# relays0_jaanuse-raal_s_conflicted_copy_2.net
KiCad netlist of a schematic drawn in Altium Designer
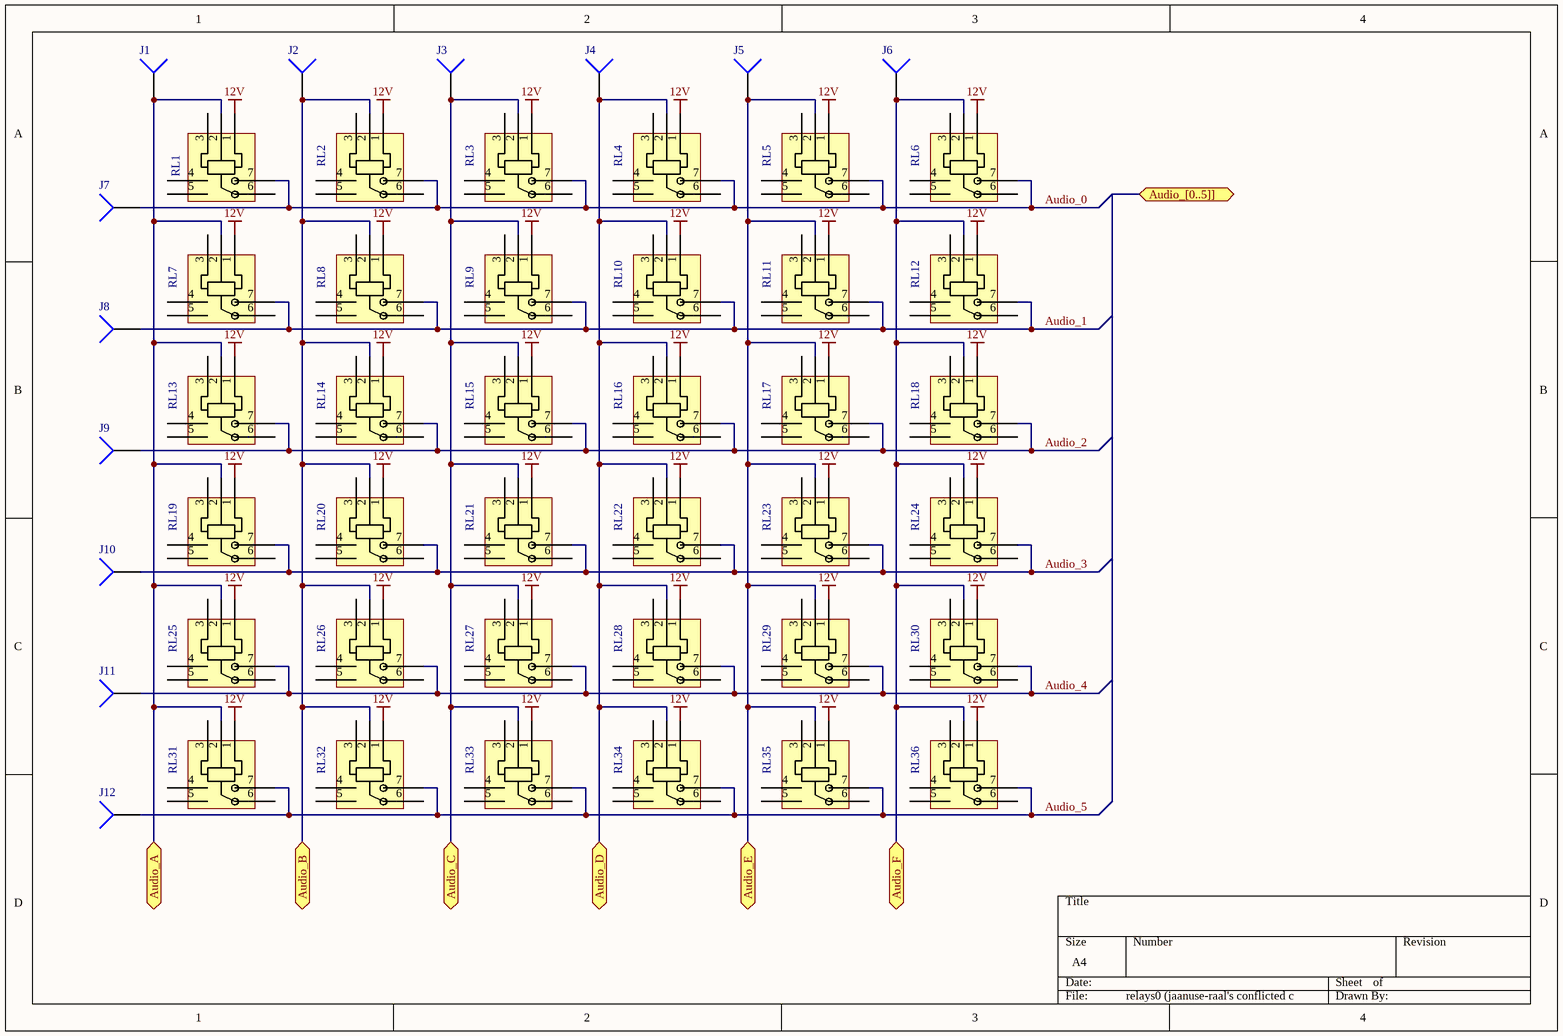
[diagram p0: relays0 (jaanuse-raal's conflicted copy 2014-11-12).SchDoc]

(export (version "E")
  (design (tool "Eeschema 10.0.6"))
  (components
    (comp (ref "J1")
      (value "Audio")
      (footprint "PIN1")
      (description "Socket")
      (fields (field (name "PUBLISHER") "Altium Limited"))
      (libsource (lib "Miscellaneous Connectors") (part "Socket"))
    )
    (comp (ref "J2")
      (value "Audio")
      (footprint "PIN1")
      (description "Socket")
      (fields (field (name "PUBLISHER") "Altium Limited"))
      (libsource (lib "Miscellaneous Connectors") (part "Socket"))
    )
    (comp (ref "J3")
      (value "Audio")
      (footprint "PIN1")
      (description "Socket")
      (fields (field (name "PUBLISHER") "Altium Limited"))
      (libsource (lib "Miscellaneous Connectors") (part "Socket"))
    )
    (comp (ref "J4")
      (value "Audio")
      (footprint "PIN1")
      (description "Socket")
      (fields (field (name "PUBLISHER") "Altium Limited"))
      (libsource (lib "Miscellaneous Connectors") (part "Socket"))
    )
    (comp (ref "J5")
      (value "Audio")
      (footprint "PIN1")
      (description "Socket")
      (fields (field (name "PUBLISHER") "Altium Limited"))
      (libsource (lib "Miscellaneous Connectors") (part "Socket"))
    )
    (comp (ref "J6")
      (value "Audio")
      (footprint "PIN1")
      (description "Socket")
      (fields (field (name "PUBLISHER") "Altium Limited"))
      (libsource (lib "Miscellaneous Connectors") (part "Socket"))
    )
    (comp (ref "J7")
      (value "Audio")
      (footprint "PIN1")
      (description "Socket")
      (fields (field (name "PUBLISHER") "Altium Limited"))
      (libsource (lib "Miscellaneous Connectors") (part "Socket"))
    )
    (comp (ref "J8")
      (value "Audio")
      (footprint "PIN1")
      (description "Socket")
      (fields (field (name "PUBLISHER") "Altium Limited"))
      (libsource (lib "Miscellaneous Connectors") (part "Socket"))
    )
    (comp (ref "J9")
      (value "Audio")
      (footprint "PIN1")
      (description "Socket")
      (fields (field (name "PUBLISHER") "Altium Limited"))
      (libsource (lib "Miscellaneous Connectors") (part "Socket"))
    )
    (comp (ref "J10")
      (value "Audio")
      (footprint "PIN1")
      (description "Socket")
      (fields (field (name "PUBLISHER") "Altium Limited"))
      (libsource (lib "Miscellaneous Connectors") (part "Socket"))
    )
    (comp (ref "J11")
      (value "Audio")
      (footprint "PIN1")
      (description "Socket")
      (fields (field (name "PUBLISHER") "Altium Limited"))
      (libsource (lib "Miscellaneous Connectors") (part "Socket"))
    )
    (comp (ref "J12")
      (value "Audio")
      (footprint "PIN1")
      (description "Socket")
      (fields (field (name "PUBLISHER") "Altium Limited"))
      (libsource (lib "Miscellaneous Connectors") (part "Socket"))
    )
    (comp (ref "RL1")
      (value "Relay")
      (footprint "Relay_FRA3")
      (description "Miniature power relay")
      (fields (field (name "PART NUMBER") "FRA3C-DC12"))
      (libsource (lib "tech-thing") (part "Relay_FRA3"))
    )
    (comp (ref "RL2")
      (value "Relay")
      (footprint "Relay_FRA3")
      (description "Miniature power relay")
      (fields (field (name "PART NUMBER") "FRA3C-DC12"))
      (libsource (lib "tech-thing") (part "Relay_FRA3"))
    )
    (comp (ref "RL3")
      (value "Relay")
      (footprint "Relay_FRA3")
      (description "Miniature power relay")
      (fields (field (name "PART NUMBER") "FRA3C-DC12"))
      (libsource (lib "tech-thing") (part "Relay_FRA3"))
    )
    (comp (ref "RL4")
      (value "Relay")
      (footprint "Relay_FRA3")
      (description "Miniature power relay")
      (fields (field (name "PART NUMBER") "FRA3C-DC12"))
      (libsource (lib "tech-thing") (part "Relay_FRA3"))
    )
    (comp (ref "RL5")
      (value "Relay")
      (footprint "Relay_FRA3")
      (description "Miniature power relay")
      (fields (field (name "PART NUMBER") "FRA3C-DC12"))
      (libsource (lib "tech-thing") (part "Relay_FRA3"))
    )
    (comp (ref "RL6")
      (value "Relay")
      (footprint "Relay_FRA3")
      (description "Miniature power relay")
      (fields (field (name "PART NUMBER") "FRA3C-DC12"))
      (libsource (lib "tech-thing") (part "Relay_FRA3"))
    )
    (comp (ref "RL7")
      (value "Relay")
      (footprint "Relay_FRA3")
      (description "Miniature power relay")
      (fields (field (name "PART NUMBER") "FRA3C-DC12"))
      (libsource (lib "tech-thing") (part "Relay_FRA3"))
    )
    (comp (ref "RL8")
      (value "Relay")
      (footprint "Relay_FRA3")
      (description "Miniature power relay")
      (fields (field (name "PART NUMBER") "FRA3C-DC12"))
      (libsource (lib "tech-thing") (part "Relay_FRA3"))
    )
    (comp (ref "RL9")
      (value "Relay")
      (footprint "Relay_FRA3")
      (description "Miniature power relay")
      (fields (field (name "PART NUMBER") "FRA3C-DC12"))
      (libsource (lib "tech-thing") (part "Relay_FRA3"))
    )
    (comp (ref "RL10")
      (value "Relay")
      (footprint "Relay_FRA3")
      (description "Miniature power relay")
      (fields (field (name "PART NUMBER") "FRA3C-DC12"))
      (libsource (lib "tech-thing") (part "Relay_FRA3"))
    )
    (comp (ref "RL11")
      (value "Relay")
      (footprint "Relay_FRA3")
      (description "Miniature power relay")
      (fields (field (name "PART NUMBER") "FRA3C-DC12"))
      (libsource (lib "tech-thing") (part "Relay_FRA3"))
    )
    (comp (ref "RL12")
      (value "Relay")
      (footprint "Relay_FRA3")
      (description "Miniature power relay")
      (fields (field (name "PART NUMBER") "FRA3C-DC12"))
      (libsource (lib "tech-thing") (part "Relay_FRA3"))
    )
    (comp (ref "RL13")
      (value "Relay")
      (footprint "Relay_FRA3")
      (description "Miniature power relay")
      (fields (field (name "PART NUMBER") "FRA3C-DC12"))
      (libsource (lib "tech-thing") (part "Relay_FRA3"))
    )
    (comp (ref "RL14")
      (value "Relay")
      (footprint "Relay_FRA3")
      (description "Miniature power relay")
      (fields (field (name "PART NUMBER") "FRA3C-DC12"))
      (libsource (lib "tech-thing") (part "Relay_FRA3"))
    )
    (comp (ref "RL15")
      (value "Relay")
      (footprint "Relay_FRA3")
      (description "Miniature power relay")
      (fields (field (name "PART NUMBER") "FRA3C-DC12"))
      (libsource (lib "tech-thing") (part "Relay_FRA3"))
    )
    (comp (ref "RL16")
      (value "Relay")
      (footprint "Relay_FRA3")
      (description "Miniature power relay")
      (fields (field (name "PART NUMBER") "FRA3C-DC12"))
      (libsource (lib "tech-thing") (part "Relay_FRA3"))
    )
    (comp (ref "RL17")
      (value "Relay")
      (footprint "Relay_FRA3")
      (description "Miniature power relay")
      (fields (field (name "PART NUMBER") "FRA3C-DC12"))
      (libsource (lib "tech-thing") (part "Relay_FRA3"))
    )
    (comp (ref "RL18")
      (value "Relay")
      (footprint "Relay_FRA3")
      (description "Miniature power relay")
      (fields (field (name "PART NUMBER") "FRA3C-DC12"))
      (libsource (lib "tech-thing") (part "Relay_FRA3"))
    )
    (comp (ref "RL19")
      (value "Relay")
      (footprint "Relay_FRA3")
      (description "Miniature power relay")
      (fields (field (name "PART NUMBER") "FRA3C-DC12"))
      (libsource (lib "tech-thing") (part "Relay_FRA3"))
    )
    (comp (ref "RL20")
      (value "Relay")
      (footprint "Relay_FRA3")
      (description "Miniature power relay")
      (fields (field (name "PART NUMBER") "FRA3C-DC12"))
      (libsource (lib "tech-thing") (part "Relay_FRA3"))
    )
    (comp (ref "RL21")
      (value "Relay")
      (footprint "Relay_FRA3")
      (description "Miniature power relay")
      (fields (field (name "PART NUMBER") "FRA3C-DC12"))
      (libsource (lib "tech-thing") (part "Relay_FRA3"))
    )
    (comp (ref "RL22")
      (value "Relay")
      (footprint "Relay_FRA3")
      (description "Miniature power relay")
      (fields (field (name "PART NUMBER") "FRA3C-DC12"))
      (libsource (lib "tech-thing") (part "Relay_FRA3"))
    )
    (comp (ref "RL23")
      (value "Relay")
      (footprint "Relay_FRA3")
      (description "Miniature power relay")
      (fields (field (name "PART NUMBER") "FRA3C-DC12"))
      (libsource (lib "tech-thing") (part "Relay_FRA3"))
    )
    (comp (ref "RL24")
      (value "Relay")
      (footprint "Relay_FRA3")
      (description "Miniature power relay")
      (fields (field (name "PART NUMBER") "FRA3C-DC12"))
      (libsource (lib "tech-thing") (part "Relay_FRA3"))
    )
    (comp (ref "RL25")
      (value "Relay")
      (footprint "Relay_FRA3")
      (description "Miniature power relay")
      (fields (field (name "PART NUMBER") "FRA3C-DC12"))
      (libsource (lib "tech-thing") (part "Relay_FRA3"))
    )
    (comp (ref "RL26")
      (value "Relay")
      (footprint "Relay_FRA3")
      (description "Miniature power relay")
      (fields (field (name "PART NUMBER") "FRA3C-DC12"))
      (libsource (lib "tech-thing") (part "Relay_FRA3"))
    )
    (comp (ref "RL27")
      (value "Relay")
      (footprint "Relay_FRA3")
      (description "Miniature power relay")
      (fields (field (name "PART NUMBER") "FRA3C-DC12"))
      (libsource (lib "tech-thing") (part "Relay_FRA3"))
    )
    (comp (ref "RL28")
      (value "Relay")
      (footprint "Relay_FRA3")
      (description "Miniature power relay")
      (fields (field (name "PART NUMBER") "FRA3C-DC12"))
      (libsource (lib "tech-thing") (part "Relay_FRA3"))
    )
    (comp (ref "RL29")
      (value "Relay")
      (footprint "Relay_FRA3")
      (description "Miniature power relay")
      (fields (field (name "PART NUMBER") "FRA3C-DC12"))
      (libsource (lib "tech-thing") (part "Relay_FRA3"))
    )
    (comp (ref "RL30")
      (value "Relay")
      (footprint "Relay_FRA3")
      (description "Miniature power relay")
      (fields (field (name "PART NUMBER") "FRA3C-DC12"))
      (libsource (lib "tech-thing") (part "Relay_FRA3"))
    )
    (comp (ref "RL31")
      (value "Relay")
      (footprint "Relay_FRA3")
      (description "Miniature power relay")
      (fields (field (name "PART NUMBER") "FRA3C-DC12"))
      (libsource (lib "tech-thing") (part "Relay_FRA3"))
    )
    (comp (ref "RL32")
      (value "Relay")
      (footprint "Relay_FRA3")
      (description "Miniature power relay")
      (fields (field (name "PART NUMBER") "FRA3C-DC12"))
      (libsource (lib "tech-thing") (part "Relay_FRA3"))
    )
    (comp (ref "RL33")
      (value "Relay")
      (footprint "Relay_FRA3")
      (description "Miniature power relay")
      (fields (field (name "PART NUMBER") "FRA3C-DC12"))
      (libsource (lib "tech-thing") (part "Relay_FRA3"))
    )
    (comp (ref "RL34")
      (value "Relay")
      (footprint "Relay_FRA3")
      (description "Miniature power relay")
      (fields (field (name "PART NUMBER") "FRA3C-DC12"))
      (libsource (lib "tech-thing") (part "Relay_FRA3"))
    )
    (comp (ref "RL35")
      (value "Relay")
      (footprint "Relay_FRA3")
      (description "Miniature power relay")
      (fields (field (name "PART NUMBER") "FRA3C-DC12"))
      (libsource (lib "tech-thing") (part "Relay_FRA3"))
    )
    (comp (ref "RL36")
      (value "Relay")
      (footprint "Relay_FRA3")
      (description "Miniature power relay")
      (fields (field (name "PART NUMBER") "FRA3C-DC12"))
      (libsource (lib "tech-thing") (part "Relay_FRA3"))
    )
  )
  (nets
    (net (code "1") (name "/Audio_0") (class "Default")
      (node (ref "J7") (pin "1") (pinfunction "1_1") (pintype "passive"))
      (node (ref "RL1") (pin "7") (pintype "passive"))
      (node (ref "RL2") (pin "7") (pintype "passive"))
      (node (ref "RL3") (pin "7") (pintype "passive"))
      (node (ref "RL4") (pin "7") (pintype "passive"))
      (node (ref "RL5") (pin "7") (pintype "passive"))
      (node (ref "RL6") (pin "7") (pintype "passive"))
    )
    (net (code "2") (name "/Audio_1") (class "Default")
      (node (ref "J8") (pin "1") (pinfunction "1_1") (pintype "passive"))
      (node (ref "RL10") (pin "7") (pintype "passive"))
      (node (ref "RL11") (pin "7") (pintype "passive"))
      (node (ref "RL12") (pin "7") (pintype "passive"))
      (node (ref "RL7") (pin "7") (pintype "passive"))
      (node (ref "RL8") (pin "7") (pintype "passive"))
      (node (ref "RL9") (pin "7") (pintype "passive"))
    )
    (net (code "3") (name "/Audio_2") (class "Default")
      (node (ref "J9") (pin "1") (pinfunction "1_1") (pintype "passive"))
      (node (ref "RL13") (pin "7") (pintype "passive"))
      (node (ref "RL14") (pin "7") (pintype "passive"))
      (node (ref "RL15") (pin "7") (pintype "passive"))
      (node (ref "RL16") (pin "7") (pintype "passive"))
      (node (ref "RL17") (pin "7") (pintype "passive"))
      (node (ref "RL18") (pin "7") (pintype "passive"))
    )
    (net (code "4") (name "/Audio_3") (class "Default")
      (node (ref "J10") (pin "1") (pinfunction "1_1") (pintype "passive"))
      (node (ref "RL19") (pin "7") (pintype "passive"))
      (node (ref "RL20") (pin "7") (pintype "passive"))
      (node (ref "RL21") (pin "7") (pintype "passive"))
      (node (ref "RL22") (pin "7") (pintype "passive"))
      (node (ref "RL23") (pin "7") (pintype "passive"))
      (node (ref "RL24") (pin "7") (pintype "passive"))
    )
    (net (code "5") (name "/Audio_4") (class "Default")
      (node (ref "J11") (pin "1") (pinfunction "1_1") (pintype "passive"))
      (node (ref "RL25") (pin "7") (pintype "passive"))
      (node (ref "RL26") (pin "7") (pintype "passive"))
      (node (ref "RL27") (pin "7") (pintype "passive"))
      (node (ref "RL28") (pin "7") (pintype "passive"))
      (node (ref "RL29") (pin "7") (pintype "passive"))
      (node (ref "RL30") (pin "7") (pintype "passive"))
    )
    (net (code "6") (name "/Audio_5") (class "Default")
      (node (ref "J12") (pin "1") (pinfunction "1_1") (pintype "passive"))
      (node (ref "RL31") (pin "7") (pintype "passive"))
      (node (ref "RL32") (pin "7") (pintype "passive"))
      (node (ref "RL33") (pin "7") (pintype "passive"))
      (node (ref "RL34") (pin "7") (pintype "passive"))
      (node (ref "RL35") (pin "7") (pintype "passive"))
      (node (ref "RL36") (pin "7") (pintype "passive"))
    )
    (net (code "7") (name "/Audio_A") (class "Default")
      (node (ref "J1") (pin "1") (pinfunction "1_1") (pintype "passive"))
      (node (ref "RL1") (pin "2") (pintype "passive"))
      (node (ref "RL13") (pin "2") (pintype "passive"))
      (node (ref "RL19") (pin "2") (pintype "passive"))
      (node (ref "RL25") (pin "2") (pintype "passive"))
      (node (ref "RL31") (pin "2") (pintype "passive"))
      (node (ref "RL7") (pin "2") (pintype "passive"))
    )
    (net (code "8") (name "/Audio_B") (class "Default")
      (node (ref "J2") (pin "1") (pinfunction "1_1") (pintype "passive"))
      (node (ref "RL14") (pin "2") (pintype "passive"))
      (node (ref "RL2") (pin "2") (pintype "passive"))
      (node (ref "RL20") (pin "2") (pintype "passive"))
      (node (ref "RL26") (pin "2") (pintype "passive"))
      (node (ref "RL32") (pin "2") (pintype "passive"))
      (node (ref "RL8") (pin "2") (pintype "passive"))
    )
    (net (code "9") (name "/Audio_C") (class "Default")
      (node (ref "J3") (pin "1") (pinfunction "1_1") (pintype "passive"))
      (node (ref "RL15") (pin "2") (pintype "passive"))
      (node (ref "RL21") (pin "2") (pintype "passive"))
      (node (ref "RL27") (pin "2") (pintype "passive"))
      (node (ref "RL3") (pin "2") (pintype "passive"))
      (node (ref "RL33") (pin "2") (pintype "passive"))
      (node (ref "RL9") (pin "2") (pintype "passive"))
    )
    (net (code "10") (name "/Audio_D") (class "Default")
      (node (ref "J4") (pin "1") (pinfunction "1_1") (pintype "passive"))
      (node (ref "RL10") (pin "2") (pintype "passive"))
      (node (ref "RL16") (pin "2") (pintype "passive"))
      (node (ref "RL22") (pin "2") (pintype "passive"))
      (node (ref "RL28") (pin "2") (pintype "passive"))
      (node (ref "RL34") (pin "2") (pintype "passive"))
      (node (ref "RL4") (pin "2") (pintype "passive"))
    )
    (net (code "11") (name "/Audio_E") (class "Default")
      (node (ref "J5") (pin "1") (pinfunction "1_1") (pintype "passive"))
      (node (ref "RL11") (pin "2") (pintype "passive"))
      (node (ref "RL17") (pin "2") (pintype "passive"))
      (node (ref "RL23") (pin "2") (pintype "passive"))
      (node (ref "RL29") (pin "2") (pintype "passive"))
      (node (ref "RL35") (pin "2") (pintype "passive"))
      (node (ref "RL5") (pin "2") (pintype "passive"))
    )
    (net (code "12") (name "/Audio_F") (class "Default")
      (node (ref "J6") (pin "1") (pinfunction "1_1") (pintype "passive"))
      (node (ref "RL12") (pin "2") (pintype "passive"))
      (node (ref "RL18") (pin "2") (pintype "passive"))
      (node (ref "RL24") (pin "2") (pintype "passive"))
      (node (ref "RL30") (pin "2") (pintype "passive"))
      (node (ref "RL36") (pin "2") (pintype "passive"))
      (node (ref "RL6") (pin "2") (pintype "passive"))
    )
    (net (code "14") (name "12V") (class "Default")
      (node (ref "RL1") (pin "1") (pintype "passive"))
      (node (ref "RL10") (pin "1") (pintype "passive"))
      (node (ref "RL11") (pin "1") (pintype "passive"))
      (node (ref "RL12") (pin "1") (pintype "passive"))
      (node (ref "RL13") (pin "1") (pintype "passive"))
      (node (ref "RL14") (pin "1") (pintype "passive"))
      (node (ref "RL15") (pin "1") (pintype "passive"))
      (node (ref "RL16") (pin "1") (pintype "passive"))
      (node (ref "RL17") (pin "1") (pintype "passive"))
      (node (ref "RL18") (pin "1") (pintype "passive"))
      (node (ref "RL19") (pin "1") (pintype "passive"))
      (node (ref "RL2") (pin "1") (pintype "passive"))
      (node (ref "RL20") (pin "1") (pintype "passive"))
      (node (ref "RL21") (pin "1") (pintype "passive"))
      (node (ref "RL22") (pin "1") (pintype "passive"))
      (node (ref "RL23") (pin "1") (pintype "passive"))
      (node (ref "RL24") (pin "1") (pintype "passive"))
      (node (ref "RL25") (pin "1") (pintype "passive"))
      (node (ref "RL26") (pin "1") (pintype "passive"))
      (node (ref "RL27") (pin "1") (pintype "passive"))
      (node (ref "RL28") (pin "1") (pintype "passive"))
      (node (ref "RL29") (pin "1") (pintype "passive"))
      (node (ref "RL3") (pin "1") (pintype "passive"))
      (node (ref "RL30") (pin "1") (pintype "passive"))
      (node (ref "RL31") (pin "1") (pintype "passive"))
      (node (ref "RL32") (pin "1") (pintype "passive"))
      (node (ref "RL33") (pin "1") (pintype "passive"))
      (node (ref "RL34") (pin "1") (pintype "passive"))
      (node (ref "RL35") (pin "1") (pintype "passive"))
      (node (ref "RL36") (pin "1") (pintype "passive"))
      (node (ref "RL4") (pin "1") (pintype "passive"))
      (node (ref "RL5") (pin "1") (pintype "passive"))
      (node (ref "RL6") (pin "1") (pintype "passive"))
      (node (ref "RL7") (pin "1") (pintype "passive"))
      (node (ref "RL8") (pin "1") (pintype "passive"))
      (node (ref "RL9") (pin "1") (pintype "passive"))
    )
    (net (code "15") (name "unconnected-(RL1-Pad3)") (class "Default")
      (node (ref "RL1") (pin "3") (pintype "passive"))
    )
    (net (code "16") (name "unconnected-(RL1-Pad4)") (class "Default")
      (node (ref "RL1") (pin "4") (pintype "passive"))
    )
    (net (code "17") (name "unconnected-(RL1-Pad5)") (class "Default")
      (node (ref "RL1") (pin "5") (pintype "passive"))
    )
    (net (code "18") (name "unconnected-(RL1-Pad6)") (class "Default")
      (node (ref "RL1") (pin "6") (pintype "passive"))
    )
    (net (code "19") (name "unconnected-(RL2-Pad3)") (class "Default")
      (node (ref "RL2") (pin "3") (pintype "passive"))
    )
    (net (code "20") (name "unconnected-(RL2-Pad4)") (class "Default")
      (node (ref "RL2") (pin "4") (pintype "passive"))
    )
    (net (code "21") (name "unconnected-(RL2-Pad5)") (class "Default")
      (node (ref "RL2") (pin "5") (pintype "passive"))
    )
    (net (code "22") (name "unconnected-(RL2-Pad6)") (class "Default")
      (node (ref "RL2") (pin "6") (pintype "passive"))
    )
    (net (code "23") (name "unconnected-(RL3-Pad3)") (class "Default")
      (node (ref "RL3") (pin "3") (pintype "passive"))
    )
    (net (code "24") (name "unconnected-(RL3-Pad4)") (class "Default")
      (node (ref "RL3") (pin "4") (pintype "passive"))
    )
    (net (code "25") (name "unconnected-(RL3-Pad5)") (class "Default")
      (node (ref "RL3") (pin "5") (pintype "passive"))
    )
    (net (code "26") (name "unconnected-(RL3-Pad6)") (class "Default")
      (node (ref "RL3") (pin "6") (pintype "passive"))
    )
    (net (code "27") (name "unconnected-(RL4-Pad3)") (class "Default")
      (node (ref "RL4") (pin "3") (pintype "passive"))
    )
    (net (code "28") (name "unconnected-(RL4-Pad4)") (class "Default")
      (node (ref "RL4") (pin "4") (pintype "passive"))
    )
    (net (code "29") (name "unconnected-(RL4-Pad5)") (class "Default")
      (node (ref "RL4") (pin "5") (pintype "passive"))
    )
    (net (code "30") (name "unconnected-(RL4-Pad6)") (class "Default")
      (node (ref "RL4") (pin "6") (pintype "passive"))
    )
    (net (code "31") (name "unconnected-(RL5-Pad3)") (class "Default")
      (node (ref "RL5") (pin "3") (pintype "passive"))
    )
    (net (code "32") (name "unconnected-(RL5-Pad4)") (class "Default")
      (node (ref "RL5") (pin "4") (pintype "passive"))
    )
    (net (code "33") (name "unconnected-(RL5-Pad5)") (class "Default")
      (node (ref "RL5") (pin "5") (pintype "passive"))
    )
    (net (code "34") (name "unconnected-(RL5-Pad6)") (class "Default")
      (node (ref "RL5") (pin "6") (pintype "passive"))
    )
    (net (code "35") (name "unconnected-(RL6-Pad3)") (class "Default")
      (node (ref "RL6") (pin "3") (pintype "passive"))
    )
    (net (code "36") (name "unconnected-(RL6-Pad4)") (class "Default")
      (node (ref "RL6") (pin "4") (pintype "passive"))
    )
    (net (code "37") (name "unconnected-(RL6-Pad5)") (class "Default")
      (node (ref "RL6") (pin "5") (pintype "passive"))
    )
    (net (code "38") (name "unconnected-(RL6-Pad6)") (class "Default")
      (node (ref "RL6") (pin "6") (pintype "passive"))
    )
    (net (code "39") (name "unconnected-(RL7-Pad3)") (class "Default")
      (node (ref "RL7") (pin "3") (pintype "passive"))
    )
    (net (code "40") (name "unconnected-(RL7-Pad4)") (class "Default")
      (node (ref "RL7") (pin "4") (pintype "passive"))
    )
    (net (code "41") (name "unconnected-(RL7-Pad5)") (class "Default")
      (node (ref "RL7") (pin "5") (pintype "passive"))
    )
    (net (code "42") (name "unconnected-(RL7-Pad6)") (class "Default")
      (node (ref "RL7") (pin "6") (pintype "passive"))
    )
    (net (code "43") (name "unconnected-(RL8-Pad3)") (class "Default")
      (node (ref "RL8") (pin "3") (pintype "passive"))
    )
    (net (code "44") (name "unconnected-(RL8-Pad4)") (class "Default")
      (node (ref "RL8") (pin "4") (pintype "passive"))
    )
    (net (code "45") (name "unconnected-(RL8-Pad5)") (class "Default")
      (node (ref "RL8") (pin "5") (pintype "passive"))
    )
    (net (code "46") (name "unconnected-(RL8-Pad6)") (class "Default")
      (node (ref "RL8") (pin "6") (pintype "passive"))
    )
    (net (code "47") (name "unconnected-(RL9-Pad3)") (class "Default")
      (node (ref "RL9") (pin "3") (pintype "passive"))
    )
    (net (code "48") (name "unconnected-(RL9-Pad4)") (class "Default")
      (node (ref "RL9") (pin "4") (pintype "passive"))
    )
    (net (code "49") (name "unconnected-(RL9-Pad5)") (class "Default")
      (node (ref "RL9") (pin "5") (pintype "passive"))
    )
    (net (code "50") (name "unconnected-(RL9-Pad6)") (class "Default")
      (node (ref "RL9") (pin "6") (pintype "passive"))
    )
    (net (code "51") (name "unconnected-(RL10-Pad3)") (class "Default")
      (node (ref "RL10") (pin "3") (pintype "passive"))
    )
    (net (code "52") (name "unconnected-(RL10-Pad4)") (class "Default")
      (node (ref "RL10") (pin "4") (pintype "passive"))
    )
    (net (code "53") (name "unconnected-(RL10-Pad5)") (class "Default")
      (node (ref "RL10") (pin "5") (pintype "passive"))
    )
    (net (code "54") (name "unconnected-(RL10-Pad6)") (class "Default")
      (node (ref "RL10") (pin "6") (pintype "passive"))
    )
    (net (code "55") (name "unconnected-(RL11-Pad3)") (class "Default")
      (node (ref "RL11") (pin "3") (pintype "passive"))
    )
    (net (code "56") (name "unconnected-(RL11-Pad4)") (class "Default")
      (node (ref "RL11") (pin "4") (pintype "passive"))
    )
    (net (code "57") (name "unconnected-(RL11-Pad5)") (class "Default")
      (node (ref "RL11") (pin "5") (pintype "passive"))
    )
    (net (code "58") (name "unconnected-(RL11-Pad6)") (class "Default")
      (node (ref "RL11") (pin "6") (pintype "passive"))
    )
    (net (code "59") (name "unconnected-(RL12-Pad3)") (class "Default")
      (node (ref "RL12") (pin "3") (pintype "passive"))
    )
    (net (code "60") (name "unconnected-(RL12-Pad4)") (class "Default")
      (node (ref "RL12") (pin "4") (pintype "passive"))
    )
    (net (code "61") (name "unconnected-(RL12-Pad5)") (class "Default")
      (node (ref "RL12") (pin "5") (pintype "passive"))
    )
    (net (code "62") (name "unconnected-(RL12-Pad6)") (class "Default")
      (node (ref "RL12") (pin "6") (pintype "passive"))
    )
    (net (code "63") (name "unconnected-(RL13-Pad3)") (class "Default")
      (node (ref "RL13") (pin "3") (pintype "passive"))
    )
    (net (code "64") (name "unconnected-(RL13-Pad4)") (class "Default")
      (node (ref "RL13") (pin "4") (pintype "passive"))
    )
    (net (code "65") (name "unconnected-(RL13-Pad5)") (class "Default")
      (node (ref "RL13") (pin "5") (pintype "passive"))
    )
    (net (code "66") (name "unconnected-(RL13-Pad6)") (class "Default")
      (node (ref "RL13") (pin "6") (pintype "passive"))
    )
    (net (code "67") (name "unconnected-(RL14-Pad3)") (class "Default")
      (node (ref "RL14") (pin "3") (pintype "passive"))
    )
    (net (code "68") (name "unconnected-(RL14-Pad4)") (class "Default")
      (node (ref "RL14") (pin "4") (pintype "passive"))
    )
    (net (code "69") (name "unconnected-(RL14-Pad5)") (class "Default")
      (node (ref "RL14") (pin "5") (pintype "passive"))
    )
    (net (code "70") (name "unconnected-(RL14-Pad6)") (class "Default")
      (node (ref "RL14") (pin "6") (pintype "passive"))
    )
    (net (code "71") (name "unconnected-(RL15-Pad3)") (class "Default")
      (node (ref "RL15") (pin "3") (pintype "passive"))
    )
    (net (code "72") (name "unconnected-(RL15-Pad4)") (class "Default")
      (node (ref "RL15") (pin "4") (pintype "passive"))
    )
    (net (code "73") (name "unconnected-(RL15-Pad5)") (class "Default")
      (node (ref "RL15") (pin "5") (pintype "passive"))
    )
    (net (code "74") (name "unconnected-(RL15-Pad6)") (class "Default")
      (node (ref "RL15") (pin "6") (pintype "passive"))
    )
    (net (code "75") (name "unconnected-(RL16-Pad3)") (class "Default")
      (node (ref "RL16") (pin "3") (pintype "passive"))
    )
    (net (code "76") (name "unconnected-(RL16-Pad4)") (class "Default")
      (node (ref "RL16") (pin "4") (pintype "passive"))
    )
    (net (code "77") (name "unconnected-(RL16-Pad5)") (class "Default")
      (node (ref "RL16") (pin "5") (pintype "passive"))
    )
    (net (code "78") (name "unconnected-(RL16-Pad6)") (class "Default")
      (node (ref "RL16") (pin "6") (pintype "passive"))
    )
    (net (code "79") (name "unconnected-(RL17-Pad3)") (class "Default")
      (node (ref "RL17") (pin "3") (pintype "passive"))
    )
    (net (code "80") (name "unconnected-(RL17-Pad4)") (class "Default")
      (node (ref "RL17") (pin "4") (pintype "passive"))
    )
    (net (code "81") (name "unconnected-(RL17-Pad5)") (class "Default")
      (node (ref "RL17") (pin "5") (pintype "passive"))
    )
    (net (code "82") (name "unconnected-(RL17-Pad6)") (class "Default")
      (node (ref "RL17") (pin "6") (pintype "passive"))
    )
    (net (code "83") (name "unconnected-(RL18-Pad3)") (class "Default")
      (node (ref "RL18") (pin "3") (pintype "passive"))
    )
    (net (code "84") (name "unconnected-(RL18-Pad4)") (class "Default")
      (node (ref "RL18") (pin "4") (pintype "passive"))
    )
    (net (code "85") (name "unconnected-(RL18-Pad5)") (class "Default")
      (node (ref "RL18") (pin "5") (pintype "passive"))
    )
    (net (code "86") (name "unconnected-(RL18-Pad6)") (class "Default")
      (node (ref "RL18") (pin "6") (pintype "passive"))
    )
    (net (code "87") (name "unconnected-(RL19-Pad3)") (class "Default")
      (node (ref "RL19") (pin "3") (pintype "passive"))
    )
    (net (code "88") (name "unconnected-(RL19-Pad4)") (class "Default")
      (node (ref "RL19") (pin "4") (pintype "passive"))
    )
    (net (code "89") (name "unconnected-(RL19-Pad5)") (class "Default")
      (node (ref "RL19") (pin "5") (pintype "passive"))
    )
    (net (code "90") (name "unconnected-(RL19-Pad6)") (class "Default")
      (node (ref "RL19") (pin "6") (pintype "passive"))
    )
    (net (code "91") (name "unconnected-(RL20-Pad3)") (class "Default")
      (node (ref "RL20") (pin "3") (pintype "passive"))
    )
    (net (code "92") (name "unconnected-(RL20-Pad4)") (class "Default")
      (node (ref "RL20") (pin "4") (pintype "passive"))
    )
    (net (code "93") (name "unconnected-(RL20-Pad5)") (class "Default")
      (node (ref "RL20") (pin "5") (pintype "passive"))
    )
    (net (code "94") (name "unconnected-(RL20-Pad6)") (class "Default")
      (node (ref "RL20") (pin "6") (pintype "passive"))
    )
    (net (code "95") (name "unconnected-(RL21-Pad3)") (class "Default")
      (node (ref "RL21") (pin "3") (pintype "passive"))
    )
    (net (code "96") (name "unconnected-(RL21-Pad4)") (class "Default")
      (node (ref "RL21") (pin "4") (pintype "passive"))
    )
    (net (code "97") (name "unconnected-(RL21-Pad5)") (class "Default")
      (node (ref "RL21") (pin "5") (pintype "passive"))
    )
    (net (code "98") (name "unconnected-(RL21-Pad6)") (class "Default")
      (node (ref "RL21") (pin "6") (pintype "passive"))
    )
    (net (code "99") (name "unconnected-(RL22-Pad3)") (class "Default")
      (node (ref "RL22") (pin "3") (pintype "passive"))
    )
    (net (code "100") (name "unconnected-(RL22-Pad4)") (class "Default")
      (node (ref "RL22") (pin "4") (pintype "passive"))
    )
    (net (code "101") (name "unconnected-(RL22-Pad5)") (class "Default")
      (node (ref "RL22") (pin "5") (pintype "passive"))
    )
    (net (code "102") (name "unconnected-(RL22-Pad6)") (class "Default")
      (node (ref "RL22") (pin "6") (pintype "passive"))
    )
    (net (code "103") (name "unconnected-(RL23-Pad3)") (class "Default")
      (node (ref "RL23") (pin "3") (pintype "passive"))
    )
    (net (code "104") (name "unconnected-(RL23-Pad4)") (class "Default")
      (node (ref "RL23") (pin "4") (pintype "passive"))
    )
    (net (code "105") (name "unconnected-(RL23-Pad5)") (class "Default")
      (node (ref "RL23") (pin "5") (pintype "passive"))
    )
    (net (code "106") (name "unconnected-(RL23-Pad6)") (class "Default")
      (node (ref "RL23") (pin "6") (pintype "passive"))
    )
    (net (code "107") (name "unconnected-(RL24-Pad3)") (class "Default")
      (node (ref "RL24") (pin "3") (pintype "passive"))
    )
    (net (code "108") (name "unconnected-(RL24-Pad4)") (class "Default")
      (node (ref "RL24") (pin "4") (pintype "passive"))
    )
    (net (code "109") (name "unconnected-(RL24-Pad5)") (class "Default")
      (node (ref "RL24") (pin "5") (pintype "passive"))
    )
    (net (code "110") (name "unconnected-(RL24-Pad6)") (class "Default")
      (node (ref "RL24") (pin "6") (pintype "passive"))
    )
    (net (code "111") (name "unconnected-(RL25-Pad3)") (class "Default")
      (node (ref "RL25") (pin "3") (pintype "passive"))
    )
    (net (code "112") (name "unconnected-(RL25-Pad4)") (class "Default")
      (node (ref "RL25") (pin "4") (pintype "passive"))
    )
    (net (code "113") (name "unconnected-(RL25-Pad5)") (class "Default")
      (node (ref "RL25") (pin "5") (pintype "passive"))
    )
    (net (code "114") (name "unconnected-(RL25-Pad6)") (class "Default")
      (node (ref "RL25") (pin "6") (pintype "passive"))
    )
    (net (code "115") (name "unconnected-(RL26-Pad3)") (class "Default")
      (node (ref "RL26") (pin "3") (pintype "passive"))
    )
    (net (code "116") (name "unconnected-(RL26-Pad4)") (class "Default")
      (node (ref "RL26") (pin "4") (pintype "passive"))
    )
    (net (code "117") (name "unconnected-(RL26-Pad5)") (class "Default")
      (node (ref "RL26") (pin "5") (pintype "passive"))
    )
    (net (code "118") (name "unconnected-(RL26-Pad6)") (class "Default")
      (node (ref "RL26") (pin "6") (pintype "passive"))
    )
    (net (code "119") (name "unconnected-(RL27-Pad3)") (class "Default")
      (node (ref "RL27") (pin "3") (pintype "passive"))
    )
    (net (code "120") (name "unconnected-(RL27-Pad4)") (class "Default")
      (node (ref "RL27") (pin "4") (pintype "passive"))
    )
    (net (code "121") (name "unconnected-(RL27-Pad5)") (class "Default")
      (node (ref "RL27") (pin "5") (pintype "passive"))
    )
    (net (code "122") (name "unconnected-(RL27-Pad6)") (class "Default")
      (node (ref "RL27") (pin "6") (pintype "passive"))
    )
    (net (code "123") (name "unconnected-(RL28-Pad3)") (class "Default")
      (node (ref "RL28") (pin "3") (pintype "passive"))
    )
    (net (code "124") (name "unconnected-(RL28-Pad4)") (class "Default")
      (node (ref "RL28") (pin "4") (pintype "passive"))
    )
    (net (code "125") (name "unconnected-(RL28-Pad5)") (class "Default")
      (node (ref "RL28") (pin "5") (pintype "passive"))
    )
    (net (code "126") (name "unconnected-(RL28-Pad6)") (class "Default")
      (node (ref "RL28") (pin "6") (pintype "passive"))
    )
    (net (code "127") (name "unconnected-(RL29-Pad3)") (class "Default")
      (node (ref "RL29") (pin "3") (pintype "passive"))
    )
    (net (code "128") (name "unconnected-(RL29-Pad4)") (class "Default")
      (node (ref "RL29") (pin "4") (pintype "passive"))
    )
    (net (code "129") (name "unconnected-(RL29-Pad5)") (class "Default")
      (node (ref "RL29") (pin "5") (pintype "passive"))
    )
    (net (code "130") (name "unconnected-(RL29-Pad6)") (class "Default")
      (node (ref "RL29") (pin "6") (pintype "passive"))
    )
    (net (code "131") (name "unconnected-(RL30-Pad3)") (class "Default")
      (node (ref "RL30") (pin "3") (pintype "passive"))
    )
    (net (code "132") (name "unconnected-(RL30-Pad4)") (class "Default")
      (node (ref "RL30") (pin "4") (pintype "passive"))
    )
    (net (code "133") (name "unconnected-(RL30-Pad5)") (class "Default")
      (node (ref "RL30") (pin "5") (pintype "passive"))
    )
    (net (code "134") (name "unconnected-(RL30-Pad6)") (class "Default")
      (node (ref "RL30") (pin "6") (pintype "passive"))
    )
    (net (code "135") (name "unconnected-(RL31-Pad3)") (class "Default")
      (node (ref "RL31") (pin "3") (pintype "passive"))
    )
    (net (code "136") (name "unconnected-(RL31-Pad4)") (class "Default")
      (node (ref "RL31") (pin "4") (pintype "passive"))
    )
    (net (code "137") (name "unconnected-(RL31-Pad5)") (class "Default")
      (node (ref "RL31") (pin "5") (pintype "passive"))
    )
    (net (code "138") (name "unconnected-(RL31-Pad6)") (class "Default")
      (node (ref "RL31") (pin "6") (pintype "passive"))
    )
    (net (code "139") (name "unconnected-(RL32-Pad3)") (class "Default")
      (node (ref "RL32") (pin "3") (pintype "passive"))
    )
    (net (code "140") (name "unconnected-(RL32-Pad4)") (class "Default")
      (node (ref "RL32") (pin "4") (pintype "passive"))
    )
    (net (code "141") (name "unconnected-(RL32-Pad5)") (class "Default")
      (node (ref "RL32") (pin "5") (pintype "passive"))
    )
    (net (code "142") (name "unconnected-(RL32-Pad6)") (class "Default")
      (node (ref "RL32") (pin "6") (pintype "passive"))
    )
    (net (code "143") (name "unconnected-(RL33-Pad3)") (class "Default")
      (node (ref "RL33") (pin "3") (pintype "passive"))
    )
    (net (code "144") (name "unconnected-(RL33-Pad4)") (class "Default")
      (node (ref "RL33") (pin "4") (pintype "passive"))
    )
    (net (code "145") (name "unconnected-(RL33-Pad5)") (class "Default")
      (node (ref "RL33") (pin "5") (pintype "passive"))
    )
    (net (code "146") (name "unconnected-(RL33-Pad6)") (class "Default")
      (node (ref "RL33") (pin "6") (pintype "passive"))
    )
    (net (code "147") (name "unconnected-(RL34-Pad3)") (class "Default")
      (node (ref "RL34") (pin "3") (pintype "passive"))
    )
    (net (code "148") (name "unconnected-(RL34-Pad4)") (class "Default")
      (node (ref "RL34") (pin "4") (pintype "passive"))
    )
    (net (code "149") (name "unconnected-(RL34-Pad5)") (class "Default")
      (node (ref "RL34") (pin "5") (pintype "passive"))
    )
    (net (code "150") (name "unconnected-(RL34-Pad6)") (class "Default")
      (node (ref "RL34") (pin "6") (pintype "passive"))
    )
    (net (code "151") (name "unconnected-(RL35-Pad3)") (class "Default")
      (node (ref "RL35") (pin "3") (pintype "passive"))
    )
    (net (code "152") (name "unconnected-(RL35-Pad4)") (class "Default")
      (node (ref "RL35") (pin "4") (pintype "passive"))
    )
    (net (code "153") (name "unconnected-(RL35-Pad5)") (class "Default")
      (node (ref "RL35") (pin "5") (pintype "passive"))
    )
    (net (code "154") (name "unconnected-(RL35-Pad6)") (class "Default")
      (node (ref "RL35") (pin "6") (pintype "passive"))
    )
    (net (code "155") (name "unconnected-(RL36-Pad3)") (class "Default")
      (node (ref "RL36") (pin "3") (pintype "passive"))
    )
    (net (code "156") (name "unconnected-(RL36-Pad4)") (class "Default")
      (node (ref "RL36") (pin "4") (pintype "passive"))
    )
    (net (code "157") (name "unconnected-(RL36-Pad5)") (class "Default")
      (node (ref "RL36") (pin "5") (pintype "passive"))
    )
    (net (code "158") (name "unconnected-(RL36-Pad6)") (class "Default")
      (node (ref "RL36") (pin "6") (pintype "passive"))
    )
  )
)
